# Channel.net
KiCad netlist of a schematic drawn in Altium Designer
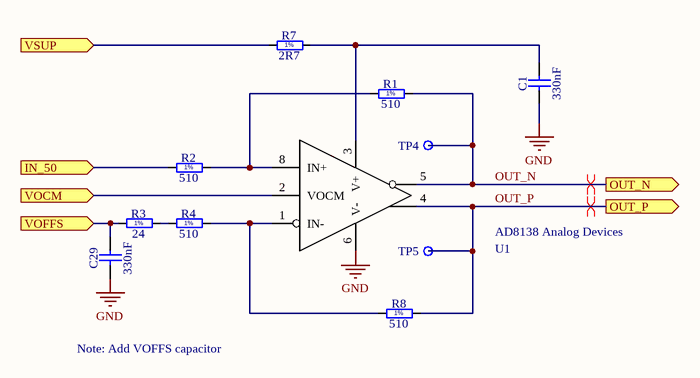
[diagram p0: Channel.SchDoc]

(export (version "E")
  (design (tool "Eeschema 10.0.6"))
  (components
    (comp (ref "C1")
      (value "330nF")
      (footprint "CAPC2012X135N")
      (description "Non-polarised capacitor")
      (fields
        (field (name "PART NUMBER") "CC0805_330NF_16V_10%_X7R")
        (field (name "VOLTAGE") "16V")
        (field (name "AUTHOR") "CERN DEM JLC")
      )
      (libsource (lib "Capacitors") (part "Capacitor - non polarized"))
    )
    (comp (ref "C29")
      (value "330nF")
      (footprint "CAPC2012X135N")
      (description "Non-polarised capacitor")
      (fields
        (field (name "PART NUMBER") "CC0805_330NF_16V_10%_X7R")
        (field (name "VOLTAGE") "16V")
        (field (name "AUTHOR") "CERN DEM JLC")
      )
      (libsource (lib "Capacitors") (part "Capacitor - non polarized"))
    )
    (comp (ref "R1")
      (value "510")
      (footprint "RESC2012X60N")
      (description "Resistor - 1%")
      (fields
        (field (name "PART NUMBER") "R0805_510R_1%_0.125W_100PPM")
        (field (name "POWER") "0.125W")
        (field (name "AUTHOR") "CERN DEM JLC")
      )
      (libsource (lib "Resistors") (part "Resistor - 1%"))
    )
    (comp (ref "R2")
      (value "510")
      (footprint "RESC2012X60N")
      (description "Resistor - 1%")
      (fields
        (field (name "PART NUMBER") "R0805_510R_1%_0.125W_100PPM")
        (field (name "POWER") "0.125W")
        (field (name "AUTHOR") "CERN DEM JLC")
      )
      (libsource (lib "Resistors") (part "Resistor - 1%"))
    )
    (comp (ref "R3")
      (value "24")
      (footprint "RESC2012X60N")
      (description "Resistor - 1%")
      (fields
        (field (name "PART NUMBER") "R0805_24R_1%_0.125W_100PPM")
        (field (name "POWER") "0.125W")
        (field (name "AUTHOR") "CERN DEM JLC")
      )
      (libsource (lib "Resistors") (part "Resistor - 1%"))
    )
    (comp (ref "R4")
      (value "510")
      (footprint "RESC2012X60N")
      (description "Resistor - 1%")
      (fields
        (field (name "PART NUMBER") "R0805_510R_1%_0.125W_100PPM")
        (field (name "POWER") "0.125W")
        (field (name "AUTHOR") "CERN DEM JLC")
      )
      (libsource (lib "Resistors") (part "Resistor - 1%"))
    )
    (comp (ref "R7")
      (value "2R7")
      (footprint "RESC2012X60N")
      (description "Resistor - 1%")
      (fields
        (field (name "PART NUMBER") "R0805_2R7_1%_0.125W_200PPM")
        (field (name "POWER") "0.125W")
        (field (name "AUTHOR") "CERN DEM JLC")
      )
      (libsource (lib "Resistors") (part "Resistor - 1%"))
    )
    (comp (ref "R8")
      (value "510")
      (footprint "RESC2012X60N")
      (description "Resistor - 1%")
      (fields
        (field (name "PART NUMBER") "R0805_510R_1%_0.125W_100PPM")
        (field (name "POWER") "0.125W")
        (field (name "AUTHOR") "CERN DEM JLC")
      )
      (libsource (lib "Resistors") (part "Resistor - 1%"))
    )
    (comp (ref "TP4")
      (value "Test Point")
      (footprint "Testpoint")
      (fields
        (field (name "PART NUMBER") "VERO_20-313145")
        (field (name "MANUFACTURER") "VERO TECHNOLOGIES")
        (field (name "MANUFACTURER PART NUMBER") "20-313145")
        (field (name "AUTHOR") "CERN DEM JLC")
      )
      (libsource (lib "Connectors") (part "Test Point"))
    )
    (comp (ref "TP5")
      (value "Test Point")
      (footprint "Testpoint")
      (fields
        (field (name "PART NUMBER") "VERO_20-313145")
        (field (name "MANUFACTURER") "VERO TECHNOLOGIES")
        (field (name "MANUFACTURER PART NUMBER") "20-313145")
        (field (name "AUTHOR") "CERN DEM JLC")
      )
      (libsource (lib "Connectors") (part "Test Point"))
    )
    (comp (ref "U1")
      (value "AD8138 Analog Devices")
      (footprint "SOIC127P600X175-8N")
      (fields (field (name "MANUFACTURER") "Analog Devices"))
      (libsource (lib "Additional") (part "AD8138"))
    )
  )
  (nets
    (net (code "1") (name "/IN_50") (class "Default")
      (node (ref "R2") (pin "1") (pinfunction "1_1") (pintype "passive"))
    )
    (net (code "2") (name "/OUT_N") (class "Default")
      (node (ref "R1") (pin "2") (pinfunction "2_2") (pintype "passive"))
      (node (ref "TP4") (pin "1") (pinfunction "1_1") (pintype "bidirectional"))
      (node (ref "U1") (pin "5") (pinfunction "OUT-_5") (pintype "passive"))
    )
    (net (code "3") (name "/OUT_P") (class "Default")
      (node (ref "R8") (pin "2") (pinfunction "2_2") (pintype "passive"))
      (node (ref "TP5") (pin "1") (pinfunction "1_1") (pintype "bidirectional"))
      (node (ref "U1") (pin "4") (pinfunction "OUT+_4") (pintype "passive"))
    )
    (net (code "4") (name "/VOCM") (class "Default")
      (node (ref "U1") (pin "2") (pinfunction "VOCM_2") (pintype "passive"))
    )
    (net (code "5") (name "/VOFFS") (class "Default")
      (node (ref "C29") (pin "2") (pinfunction "2_2") (pintype "passive"))
      (node (ref "R3") (pin "1") (pinfunction "1_1") (pintype "passive"))
    )
    (net (code "6") (name "/VSUP") (class "Default")
      (node (ref "R7") (pin "1") (pinfunction "1_1") (pintype "passive"))
    )
    (net (code "7") (name "GND") (class "Default")
      (node (ref "C1") (pin "1") (pinfunction "1_1") (pintype "passive"))
      (node (ref "C29") (pin "1") (pinfunction "1_1") (pintype "passive"))
      (node (ref "U1") (pin "6") (pinfunction "V-_6") (pintype "passive"))
    )
    (net (code "8") (name "Net-(R3-Pad2)") (class "Default")
      (node (ref "R3") (pin "2") (pinfunction "2_2") (pintype "passive"))
      (node (ref "R4") (pin "1") (pinfunction "1_1") (pintype "passive"))
    )
    (net (code "9") (name "Net-(U1-IN+)") (class "Default")
      (node (ref "R1") (pin "1") (pinfunction "1_1") (pintype "passive"))
      (node (ref "R2") (pin "2") (pinfunction "2_2") (pintype "passive"))
      (node (ref "U1") (pin "8") (pinfunction "IN+_8") (pintype "passive"))
    )
    (net (code "10") (name "Net-(U1-IN-)") (class "Default")
      (node (ref "R4") (pin "2") (pinfunction "2_2") (pintype "passive"))
      (node (ref "R8") (pin "1") (pinfunction "1_1") (pintype "passive"))
      (node (ref "U1") (pin "1") (pinfunction "IN-_1") (pintype "passive"))
    )
    (net (code "11") (name "Net-(U1-V+)") (class "Default")
      (node (ref "C1") (pin "2") (pinfunction "2_2") (pintype "passive"))
      (node (ref "R7") (pin "2") (pinfunction "2_2") (pintype "passive"))
      (node (ref "U1") (pin "3") (pinfunction "V+_3") (pintype "passive"))
    )
  )
)
